# tcam_mini_eth_base.net
KiCad netlist of a schematic drawn in EAGLE
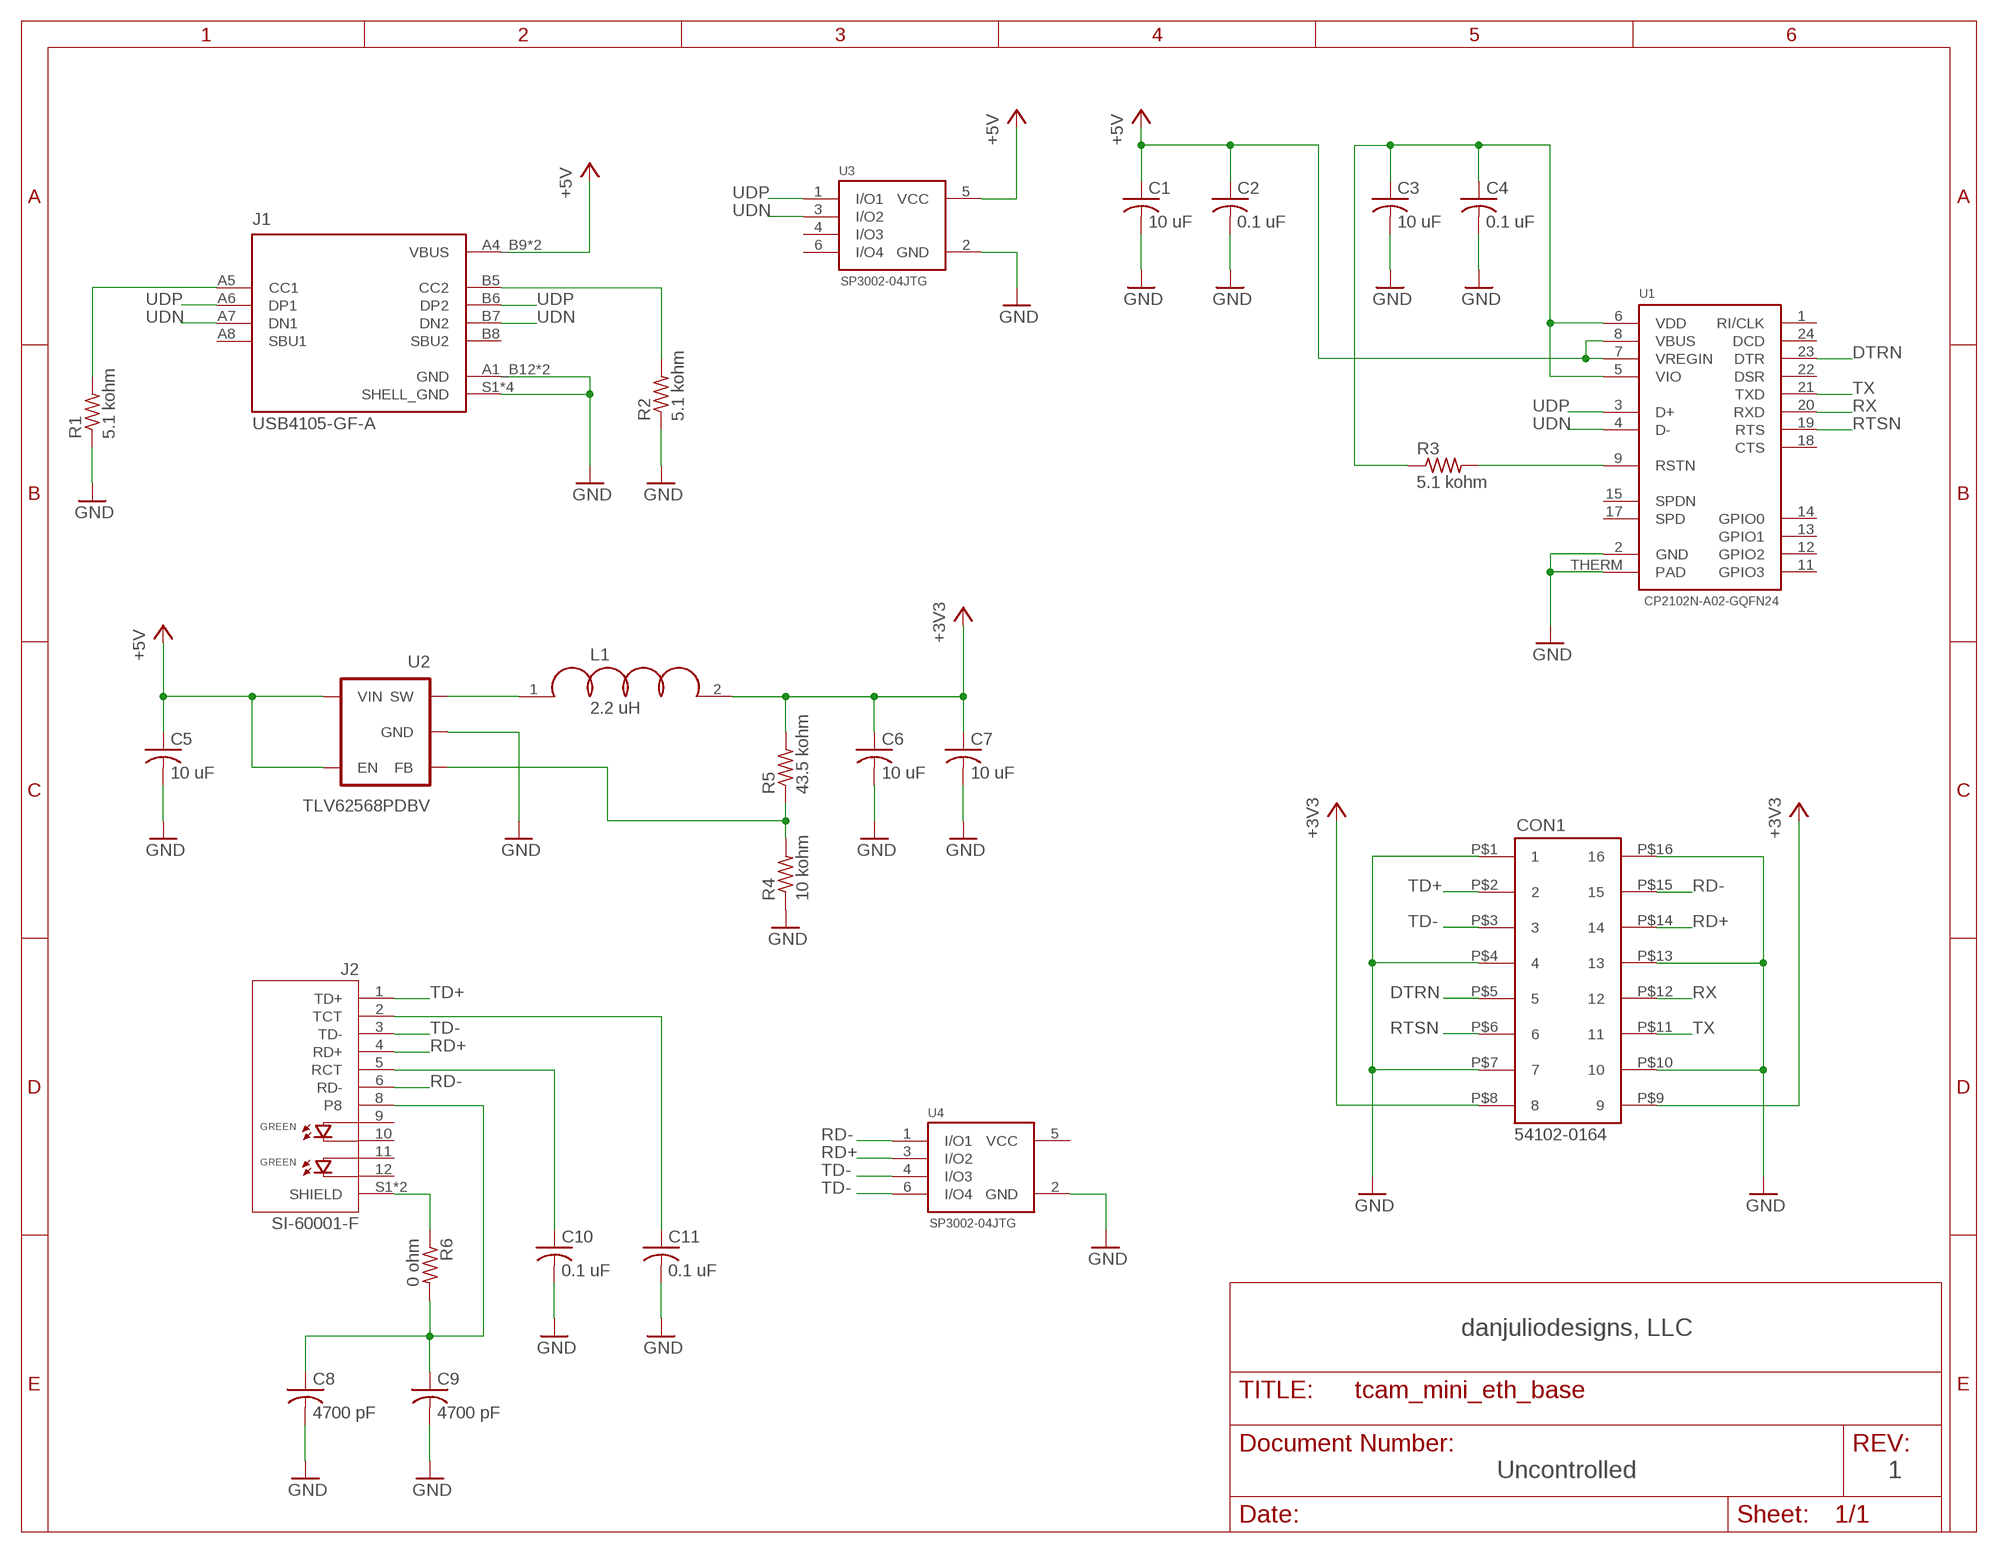
[diagram p0: schematic, sheet 1]

(export (version "E")
  (design (tool "Eeschema 10.0.6"))
  (components
    (comp (ref "C1")
      (value "10 uF")
      (footprint "eagle-import:C0603")
      (libsource (lib "eagle-import") (part "C-USSMT0603"))
    )
    (comp (ref "C2")
      (value "0.1 uF")
      (footprint "eagle-import:C0603")
      (libsource (lib "eagle-import") (part "C-USSMT0603"))
    )
    (comp (ref "C3")
      (value "10 uF")
      (footprint "eagle-import:C0603")
      (libsource (lib "eagle-import") (part "C-USSMT0603"))
    )
    (comp (ref "C4")
      (value "0.1 uF")
      (footprint "eagle-import:C0603")
      (libsource (lib "eagle-import") (part "C-USSMT0603"))
    )
    (comp (ref "C5")
      (value "10 uF")
      (footprint "eagle-import:C0603")
      (libsource (lib "eagle-import") (part "C-USSMT0603"))
    )
    (comp (ref "C6")
      (value "10 uF")
      (footprint "eagle-import:C0603")
      (libsource (lib "eagle-import") (part "C-USSMT0603"))
    )
    (comp (ref "C7")
      (value "10 uF")
      (footprint "eagle-import:C0603")
      (libsource (lib "eagle-import") (part "C-USSMT0603"))
    )
    (comp (ref "C8")
      (value "4700 pF")
      (footprint "eagle-import:C1210")
      (libsource (lib "eagle-import") (part "C-USSMT1210"))
    )
    (comp (ref "C9")
      (value "4700 pF")
      (footprint "eagle-import:C1210")
      (libsource (lib "eagle-import") (part "C-USSMT1210"))
    )
    (comp (ref "C10")
      (value "0.1 uF")
      (footprint "eagle-import:C0603")
      (libsource (lib "eagle-import") (part "C-USSMT0603"))
    )
    (comp (ref "C11")
      (value "0.1 uF")
      (footprint "eagle-import:C0603")
      (libsource (lib "eagle-import") (part "C-USSMT0603"))
    )
    (comp (ref "CON1")
      (value "54102-0164")
      (footprint "eagle-import:MOLEX_54102_0164")
      (libsource (lib "eagle-import") (part "MOLEX_54102_0164"))
    )
    (comp (ref "J1")
      (value "USB4105-GF-A")
      (footprint "eagle-import:GCT_USB4105-GF-A")
      (fields (field (name "MF") "GCT"))
      (libsource (lib "eagle-import") (part "USB4105-GF-A"))
    )
    (comp (ref "J2")
      (value "SI-60001-F")
      (footprint "eagle-import:BEL_SI-60001-F")
      (fields (field (name "MF") "Stewart Connector"))
      (libsource (lib "eagle-import") (part "SI-60001-F"))
    )
    (comp (ref "L1")
      (value "2.2 uH")
      (footprint "eagle-import:L1008")
      (libsource (lib "eagle-import") (part "INDUCTORSMT1008"))
    )
    (comp (ref "R1")
      (value "5.1 kohm")
      (footprint "eagle-import:R0603")
      (libsource (lib "eagle-import") (part "R-USSMT0603"))
    )
    (comp (ref "R2")
      (value "5.1 kohm")
      (footprint "eagle-import:R0603")
      (libsource (lib "eagle-import") (part "R-USSMT0603"))
    )
    (comp (ref "R3")
      (value "5.1 kohm")
      (footprint "eagle-import:R0603")
      (libsource (lib "eagle-import") (part "R-USSMT0603"))
    )
    (comp (ref "R4")
      (value "10 kohm")
      (footprint "eagle-import:R0603")
      (libsource (lib "eagle-import") (part "R-USSMT0603"))
    )
    (comp (ref "R5")
      (value "43.5 kohm")
      (footprint "eagle-import:R0603")
      (libsource (lib "eagle-import") (part "R-USSMT0603"))
    )
    (comp (ref "R6")
      (value "0 ohm")
      (footprint "eagle-import:R0805")
      (libsource (lib "eagle-import") (part "R-USSMT0805"))
    )
    (comp (ref "U1")
      (value "CP2102N-A02-GQFN24")
      (footprint "eagle-import:QFN24")
      (libsource (lib "eagle-import") (part "CP2102N_QFN24"))
    )
    (comp (ref "U2")
      (value "TLV62568PDBV")
      (footprint "eagle-import:SOT23-5")
      (libsource (lib "eagle-import") (part "TLV62568DBV"))
    )
    (comp (ref "U3")
      (value "SP3002-04JTG")
      (footprint "eagle-import:SOT65P220X95-6N")
      (fields (field (name "MF") "Littelfuse Inc."))
      (libsource (lib "eagle-import") (part "SP3002-04JTG"))
    )
    (comp (ref "U4")
      (value "SP3002-04JTG")
      (footprint "eagle-import:SOT65P220X95-6N")
      (fields (field (name "MF") "Littelfuse Inc."))
      (libsource (lib "eagle-import") (part "SP3002-04JTG"))
    )
  )
  (nets
    (net (code "1") (name "+3V3") (class "Default")
      (node (ref "C6") (pin "1") (pinfunction "1_1") (pintype "passive"))
      (node (ref "C7") (pin "1") (pinfunction "1_1") (pintype "passive"))
      (node (ref "CON1") (pin "P$8") (pinfunction "8_P$8") (pintype "bidirectional"))
      (node (ref "CON1") (pin "P$9") (pinfunction "9_P$9") (pintype "bidirectional"))
      (node (ref "L1") (pin "2") (pinfunction "P$2_2") (pintype "passive"))
      (node (ref "R5") (pin "2") (pinfunction "2_2") (pintype "passive"))
    )
    (net (code "2") (name "+5V") (class "Default")
      (node (ref "C1") (pin "1") (pinfunction "1_1") (pintype "passive"))
      (node (ref "C2") (pin "1") (pinfunction "1_1") (pintype "passive"))
      (node (ref "C5") (pin "1") (pinfunction "1_1") (pintype "passive"))
      (node (ref "J1") (pin "A4_B9") (pinfunction "VBUS_A4_B9") (pintype "power_in"))
      (node (ref "J1") (pin "B4_A9") (pinfunction "VBUS_B4_A9") (pintype "power_in"))
      (node (ref "U1") (pin "7") (pinfunction "VREGIN_7") (pintype "power_in"))
      (node (ref "U1") (pin "8") (pinfunction "VBUS_8") (pintype "input"))
      (node (ref "U2") (pin "1") (pinfunction "EN_1") (pintype "input"))
      (node (ref "U2") (pin "4") (pinfunction "VIN_4") (pintype "input"))
      (node (ref "U3") (pin "5") (pinfunction "VCC_5") (pintype "power_in"))
    )
    (net (code "3") (name "/DTRN") (class "Default")
      (node (ref "CON1") (pin "P$5") (pinfunction "5_P$5") (pintype "bidirectional"))
      (node (ref "U1") (pin "23") (pinfunction "DTR_23") (pintype "output"))
    )
    (net (code "4") (name "/RD+") (class "Default")
      (node (ref "CON1") (pin "P$14") (pinfunction "14_P$14") (pintype "bidirectional"))
      (node (ref "J2") (pin "4") (pinfunction "RD+_4") (pintype "passive"))
      (node (ref "U4") (pin "3") (pinfunction "I/O2_3") (pintype "bidirectional"))
    )
    (net (code "5") (name "/RD-") (class "Default")
      (node (ref "CON1") (pin "P$15") (pinfunction "15_P$15") (pintype "bidirectional"))
      (node (ref "J2") (pin "6") (pinfunction "RD-_6") (pintype "passive"))
      (node (ref "U4") (pin "1") (pinfunction "I/O1_1") (pintype "bidirectional"))
    )
    (net (code "6") (name "/RTSN") (class "Default")
      (node (ref "CON1") (pin "P$6") (pinfunction "6_P$6") (pintype "bidirectional"))
      (node (ref "U1") (pin "19") (pinfunction "RTS_19") (pintype "output"))
    )
    (net (code "7") (name "/RX") (class "Default")
      (node (ref "CON1") (pin "P$12") (pinfunction "12_P$12") (pintype "bidirectional"))
      (node (ref "U1") (pin "20") (pinfunction "RXD_20") (pintype "input"))
    )
    (net (code "8") (name "/TD+") (class "Default")
      (node (ref "CON1") (pin "P$2") (pinfunction "2_P$2") (pintype "bidirectional"))
      (node (ref "J2") (pin "1") (pinfunction "TD+_1") (pintype "passive"))
      (node (ref "U4") (pin "6") (pinfunction "I/O4_6") (pintype "bidirectional"))
    )
    (net (code "9") (name "/TD-") (class "Default")
      (node (ref "CON1") (pin "P$3") (pinfunction "3_P$3") (pintype "bidirectional"))
      (node (ref "J2") (pin "3") (pinfunction "TD-_3") (pintype "passive"))
      (node (ref "U4") (pin "4") (pinfunction "I/O3_4") (pintype "bidirectional"))
    )
    (net (code "10") (name "/TX") (class "Default")
      (node (ref "CON1") (pin "P$11") (pinfunction "11_P$11") (pintype "bidirectional"))
      (node (ref "U1") (pin "21") (pinfunction "TXD_21") (pintype "output"))
    )
    (net (code "11") (name "/UDN") (class "Default")
      (node (ref "J1") (pin "A7") (pinfunction "DN1_A7") (pintype "bidirectional"))
      (node (ref "J1") (pin "B7") (pinfunction "DN2_B7") (pintype "bidirectional"))
      (node (ref "U1") (pin "4") (pinfunction "D-_4") (pintype "bidirectional"))
      (node (ref "U3") (pin "3") (pinfunction "I/O2_3") (pintype "bidirectional"))
    )
    (net (code "12") (name "/UDP") (class "Default")
      (node (ref "J1") (pin "A6") (pinfunction "DP1_A6") (pintype "bidirectional"))
      (node (ref "J1") (pin "B6") (pinfunction "DP2_B6") (pintype "bidirectional"))
      (node (ref "U1") (pin "3") (pinfunction "D+_3") (pintype "bidirectional"))
      (node (ref "U3") (pin "1") (pinfunction "I/O1_1") (pintype "bidirectional"))
    )
    (net (code "13") (name "/VCC") (class "Default")
      (node (ref "U4") (pin "5") (pinfunction "VCC_5") (pintype "power_in"))
    )
    (net (code "14") (name "GND") (class "Default")
      (node (ref "C1") (pin "2") (pinfunction "2_2") (pintype "passive"))
      (node (ref "C10") (pin "2") (pinfunction "2_2") (pintype "passive"))
      (node (ref "C11") (pin "2") (pinfunction "2_2") (pintype "passive"))
      (node (ref "C2") (pin "2") (pinfunction "2_2") (pintype "passive"))
      (node (ref "C3") (pin "2") (pinfunction "2_2") (pintype "passive"))
      (node (ref "C4") (pin "2") (pinfunction "2_2") (pintype "passive"))
      (node (ref "C5") (pin "2") (pinfunction "2_2") (pintype "passive"))
      (node (ref "C6") (pin "2") (pinfunction "2_2") (pintype "passive"))
      (node (ref "C7") (pin "2") (pinfunction "2_2") (pintype "passive"))
      (node (ref "C8") (pin "2") (pinfunction "2_2") (pintype "passive"))
      (node (ref "C9") (pin "2") (pinfunction "2_2") (pintype "passive"))
      (node (ref "CON1") (pin "P$1") (pinfunction "1_P$1") (pintype "bidirectional"))
      (node (ref "CON1") (pin "P$10") (pinfunction "10_P$10") (pintype "bidirectional"))
      (node (ref "CON1") (pin "P$13") (pinfunction "13_P$13") (pintype "bidirectional"))
      (node (ref "CON1") (pin "P$16") (pinfunction "16_P$16") (pintype "bidirectional"))
      (node (ref "CON1") (pin "P$4") (pinfunction "4_P$4") (pintype "bidirectional"))
      (node (ref "CON1") (pin "P$7") (pinfunction "7_P$7") (pintype "bidirectional"))
      (node (ref "J1") (pin "A1_B12") (pinfunction "GND_A1_B12") (pintype "power_in"))
      (node (ref "J1") (pin "B1_A12") (pinfunction "GND_B1_A12") (pintype "power_in"))
      (node (ref "J1") (pin "S1") (pinfunction "SHELL_GND_S1") (pintype "power_in"))
      (node (ref "J1") (pin "S2") (pinfunction "SHELL_GND_S2") (pintype "power_in"))
      (node (ref "J1") (pin "S3") (pinfunction "SHELL_GND_S3") (pintype "power_in"))
      (node (ref "J1") (pin "S4") (pinfunction "SHELL_GND_S4") (pintype "power_in"))
      (node (ref "R1") (pin "1") (pinfunction "1_1") (pintype "passive"))
      (node (ref "R2") (pin "1") (pinfunction "1_1") (pintype "passive"))
      (node (ref "R4") (pin "1") (pinfunction "1_1") (pintype "passive"))
      (node (ref "U1") (pin "2") (pinfunction "GND_2") (pintype "power_in"))
      (node (ref "U1") (pin "THERM") (pinfunction "PAD_THERM") (pintype "power_in"))
      (node (ref "U2") (pin "2") (pinfunction "GND_2") (pintype "input"))
      (node (ref "U3") (pin "2") (pinfunction "GND_2") (pintype "power_in"))
      (node (ref "U4") (pin "2") (pinfunction "GND_2") (pintype "power_in"))
    )
    (net (code "15") (name "Net-(J1-CC1)") (class "Default")
      (node (ref "J1") (pin "A5") (pinfunction "CC1_A5") (pintype "bidirectional"))
      (node (ref "R1") (pin "2") (pinfunction "2_2") (pintype "passive"))
    )
    (net (code "16") (name "Net-(J1-CC2)") (class "Default")
      (node (ref "J1") (pin "B5") (pinfunction "CC2_B5") (pintype "bidirectional"))
      (node (ref "R2") (pin "2") (pinfunction "2_2") (pintype "passive"))
    )
    (net (code "17") (name "Net-(J2-P8)") (class "Default")
      (node (ref "C8") (pin "1") (pinfunction "1_1") (pintype "passive"))
      (node (ref "C9") (pin "1") (pinfunction "1_1") (pintype "passive"))
      (node (ref "J2") (pin "8") (pinfunction "P8_8") (pintype "passive"))
      (node (ref "R6") (pin "2") (pinfunction "2_2") (pintype "passive"))
    )
    (net (code "18") (name "Net-(J2-RCT)") (class "Default")
      (node (ref "C10") (pin "1") (pinfunction "1_1") (pintype "passive"))
      (node (ref "J2") (pin "5") (pinfunction "RCT_5") (pintype "passive"))
    )
    (net (code "19") (name "Net-(J2-SHIELD-PadS1)") (class "Default")
      (node (ref "J2") (pin "S1") (pinfunction "SHIELD_S1") (pintype "passive"))
      (node (ref "J2") (pin "S2") (pinfunction "SHIELD_S2") (pintype "passive"))
      (node (ref "R6") (pin "1") (pinfunction "1_1") (pintype "passive"))
    )
    (net (code "20") (name "Net-(J2-TCT)") (class "Default")
      (node (ref "C11") (pin "1") (pinfunction "1_1") (pintype "passive"))
      (node (ref "J2") (pin "2") (pinfunction "TCT_2") (pintype "passive"))
    )
    (net (code "21") (name "Net-(L1-P$1)") (class "Default")
      (node (ref "L1") (pin "1") (pinfunction "P$1_1") (pintype "passive"))
      (node (ref "U2") (pin "3") (pinfunction "SW_3") (pintype "input"))
    )
    (net (code "22") (name "Net-(U1-RSTN)") (class "Default")
      (node (ref "R3") (pin "2") (pinfunction "2_2") (pintype "passive"))
      (node (ref "U1") (pin "9") (pinfunction "RSTN_9") (pintype "input"))
    )
    (net (code "23") (name "Net-(U1-VDD)") (class "Default")
      (node (ref "C3") (pin "1") (pinfunction "1_1") (pintype "passive"))
      (node (ref "C4") (pin "1") (pinfunction "1_1") (pintype "passive"))
      (node (ref "R3") (pin "1") (pinfunction "1_1") (pintype "passive"))
      (node (ref "U1") (pin "5") (pinfunction "VIO_5") (pintype "input"))
      (node (ref "U1") (pin "6") (pinfunction "VDD_6") (pintype "power_in"))
    )
    (net (code "24") (name "Net-(U2-FB)") (class "Default")
      (node (ref "R4") (pin "2") (pinfunction "2_2") (pintype "passive"))
      (node (ref "R5") (pin "1") (pinfunction "1_1") (pintype "passive"))
      (node (ref "U2") (pin "5") (pinfunction "FB_5") (pintype "input"))
    )
    (net (code "25") (name "unconnected-(J1-SBU1-PadA8)") (class "Default")
      (node (ref "J1") (pin "A8") (pinfunction "SBU1_A8") (pintype "bidirectional"))
    )
    (net (code "26") (name "unconnected-(J1-SBU2-PadB8)") (class "Default")
      (node (ref "J1") (pin "B8") (pinfunction "SBU2_B8") (pintype "bidirectional"))
    )
    (net (code "27") (name "unconnected-(J2-GA1-Pad9)") (class "Default")
      (node (ref "J2") (pin "9") (pinfunction "GA1_9") (pintype "passive"))
    )
    (net (code "28") (name "unconnected-(J2-GA2-Pad11)") (class "Default")
      (node (ref "J2") (pin "11") (pinfunction "GA2_11") (pintype "passive"))
    )
    (net (code "29") (name "unconnected-(J2-GK1-Pad10)") (class "Default")
      (node (ref "J2") (pin "10") (pinfunction "GK1_10") (pintype "passive"))
    )
    (net (code "30") (name "unconnected-(J2-GK2-Pad12)") (class "Default")
      (node (ref "J2") (pin "12") (pinfunction "GK2_12") (pintype "passive"))
    )
    (net (code "31") (name "unconnected-(U1-CTS-Pad18)") (class "Default")
      (node (ref "U1") (pin "18") (pinfunction "CTS_18") (pintype "input"))
    )
    (net (code "32") (name "unconnected-(U1-DCD-Pad24)") (class "Default")
      (node (ref "U1") (pin "24") (pinfunction "DCD_24") (pintype "input"))
    )
    (net (code "33") (name "unconnected-(U1-DSR-Pad22)") (class "Default")
      (node (ref "U1") (pin "22") (pinfunction "DSR_22") (pintype "input"))
    )
    (net (code "34") (name "unconnected-(U1-GPIO0-Pad14)") (class "Default")
      (node (ref "U1") (pin "14") (pinfunction "GPIO0_14") (pintype "bidirectional"))
    )
    (net (code "35") (name "unconnected-(U1-GPIO1-Pad13)") (class "Default")
      (node (ref "U1") (pin "13") (pinfunction "GPIO1_13") (pintype "bidirectional"))
    )
    (net (code "36") (name "unconnected-(U1-GPIO2-Pad12)") (class "Default")
      (node (ref "U1") (pin "12") (pinfunction "GPIO2_12") (pintype "bidirectional"))
    )
    (net (code "37") (name "unconnected-(U1-GPIO3-Pad11)") (class "Default")
      (node (ref "U1") (pin "11") (pinfunction "GPIO3_11") (pintype "bidirectional"))
    )
    (net (code "38") (name "unconnected-(U1-RI{slash}CLK-Pad1)") (class "Default")
      (node (ref "U1") (pin "1") (pinfunction "RI/CLK_1") (pintype "bidirectional"))
    )
    (net (code "39") (name "unconnected-(U1-SPD-Pad17)") (class "Default")
      (node (ref "U1") (pin "17") (pinfunction "SPD_17") (pintype "output"))
    )
    (net (code "40") (name "unconnected-(U1-SPDN-Pad15)") (class "Default")
      (node (ref "U1") (pin "15") (pinfunction "SPDN_15") (pintype "output"))
    )
    (net (code "41") (name "unconnected-(U3-I{slash}O3-Pad4)") (class "Default")
      (node (ref "U3") (pin "4") (pinfunction "I/O3_4") (pintype "bidirectional"))
    )
    (net (code "42") (name "unconnected-(U3-I{slash}O4-Pad6)") (class "Default")
      (node (ref "U3") (pin "6") (pinfunction "I/O4_6") (pintype "bidirectional"))
    )
  )
)
